# Sheet1.net
KiCad netlist of a schematic drawn in Altium Designer
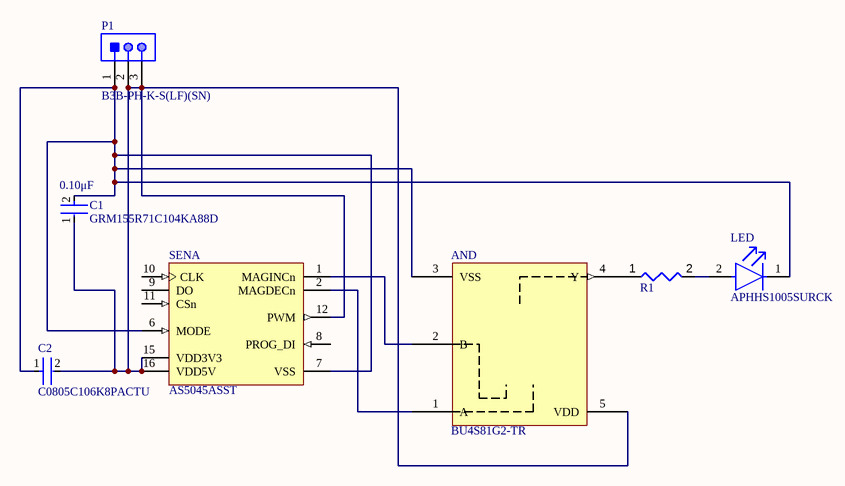
[diagram p0: Sheet1.SchDoc]

(export (version "E")
  (design (tool "Eeschema 10.0.6"))
  (components
    (comp (ref "AND")
      (value "BU4S81G2-TR")
      (footprint "TSOP95P280X125-5M")
      (description "Single 2-Input AND Gate, SSOP5, RoHS")
      (libsource (lib "FRC2021 - #604") (part "BU4S81G2-TR-Symbol-1"))
    )
    (comp (ref "C1")
      (value "GRM155R71C104KA88D")
      (footprint "FP-GRM15-MFG")
      (description "CAP CER 0.1UF 16V X7R 0402")
      (fields
        (field (name "TOLERANCE") "10%")
        (field (name "OCTOPART") "https://octopart.com/grm155r71c104ka88d-murata-196880")
        (field (name "CAPACITANCE") "0.10μF")
      )
      (libsource (lib "Altium Content Vault") (part "236180d848d6139a670b325ea6854c9"))
    )
    (comp (ref "C2")
      (value "C0805C106K8PACTU")
      (footprint "FP-C0805C-DG-MFG")
      (description "CAP CER 10UF 10V X5R 0805")
      (fields (field (name "TOLERANCE") "10%") (field (name "MANUFACTURER") "Kemet"))
      (libsource (lib "Altium Content Vault") (part "11868f565c42a9108669ba33697ecf6"))
    )
    (comp (ref "LED")
      (value "APHHS1005SURCK")
      (footprint "FP-APHHS1005SURCK-MFG")
      (description "LED RED CLEAR CHIP SMD")
      (libsource (lib "Altium Content Vault") (part "8706943c75ba83719d021d2fdc84c58"))
    )
    (comp (ref "P1")
      (value "B3B-PH-K-S(LF)(SN)")
      (footprint "JST-B3B-PH-K-S-3_V")
      (fields (field (name "MANUFACTURER") "JST"))
      (libsource (lib "Altium Content Vault") (part "CN-1P-M-R3"))
    )
    (comp (ref "R1")
      (value "RN73H1JTTD1453F100")
      (footprint "RESC1608X06M")
      (description "Res, 145K, 1%, 0.1W, 0603 Rohs Compliant: Yes")
      (libsource (lib "FRC2021 - #604") (part "RN73H1JTTD1453F100-Symbol-1"))
    )
    (comp (ref "SEN")
      (value "AS5045ASST")
      (footprint "AMS-SSOP-16-6200X5300DE_A_L")
      (description "12 Bit Programmable Magnetic Rotary Encoder, 3.3 or 5 V, SSOP-16, Pb-Free, Reel")
      (fields (field (name "MANUFACTURER") "AMS"))
      (libsource (lib "Altium Content Vault") (part "AMS-AS5045-SSOP-16"))
    )
  )
  (nets
    (net (code "1") (name "Net-(AND-A)") (class "Default")
      (node (ref "AND") (pin "1") (pinfunction "A_1") (pintype "passive"))
      (node (ref "SEN") (pin "2") (pinfunction "MAGDECn_2") (pintype "open_collector"))
    )
    (net (code "2") (name "Net-(AND-B)") (class "Default")
      (node (ref "AND") (pin "2") (pinfunction "B_2") (pintype "passive"))
      (node (ref "SEN") (pin "1") (pinfunction "MAGINCn_1") (pintype "open_collector"))
    )
    (net (code "3") (name "Net-(AND-VDD)") (class "Default")
      (node (ref "AND") (pin "5") (pinfunction "VDD_5") (pintype "power_in"))
      (node (ref "C1") (pin "1") (pinfunction "1_1") (pintype "passive"))
      (node (ref "C2") (pin "2") (pinfunction "2_2") (pintype "passive"))
      (node (ref "P1") (pin "2") (pinfunction "2_2") (pintype "passive"))
      (node (ref "P1") (pin "3") (pinfunction "3_3") (pintype "passive"))
      (node (ref "SEN") (pin "12") (pinfunction "PWM_12") (pintype "output"))
      (node (ref "SEN") (pin "15") (pinfunction "VDD3V3_15") (pintype "power_in"))
      (node (ref "SEN") (pin "16") (pinfunction "VDD5V_16") (pintype "power_in"))
    )
    (net (code "4") (name "Net-(AND-VSS)") (class "Default")
      (node (ref "AND") (pin "3") (pinfunction "VSS_3") (pintype "passive"))
      (node (ref "C1") (pin "2") (pinfunction "2_2") (pintype "passive"))
      (node (ref "C2") (pin "1") (pinfunction "1_1") (pintype "passive"))
      (node (ref "LED") (pin "1") (pinfunction "C_1") (pintype "passive"))
      (node (ref "P1") (pin "1") (pinfunction "1_1") (pintype "passive"))
      (node (ref "SEN") (pin "6") (pinfunction "MODE_6") (pintype "input"))
      (node (ref "SEN") (pin "7") (pinfunction "VSS_7") (pintype "power_in"))
    )
    (net (code "5") (name "Net-(AND-Y)") (class "Default")
      (node (ref "AND") (pin "4") (pinfunction "Y_4") (pintype "output"))
      (node (ref "R1") (pin "1") (pinfunction "1_1") (pintype "passive"))
    )
    (net (code "6") (name "Net-(LED-A)") (class "Default")
      (node (ref "LED") (pin "2") (pinfunction "A_2") (pintype "passive"))
      (node (ref "R1") (pin "2") (pinfunction "2_2") (pintype "passive"))
    )
    (net (code "7") (name "unconnected-(SENA-CLK-Pad10)") (class "Default")
      (node (ref "SEN") (pin "10") (pinfunction "CLK_10") (pintype "input"))
    )
    (net (code "8") (name "unconnected-(SENA-CSn-Pad11)") (class "Default")
      (node (ref "SEN") (pin "11") (pinfunction "CSn_11") (pintype "input"))
    )
    (net (code "9") (name "unconnected-(SENA-DO-Pad9)") (class "Default")
      (node (ref "SEN") (pin "9") (pinfunction "DO_9") (pintype "tri_state"))
    )
    (net (code "10") (name "unconnected-(SENA-PROG_DI-Pad8)") (class "Default")
      (node (ref "SEN") (pin "8") (pinfunction "PROG_DI_8") (pintype "input"))
    )
  )
)
